# CON_AUDIO_AC99_NOMIC.net
KiCad netlist of a schematic drawn in Altium Designer
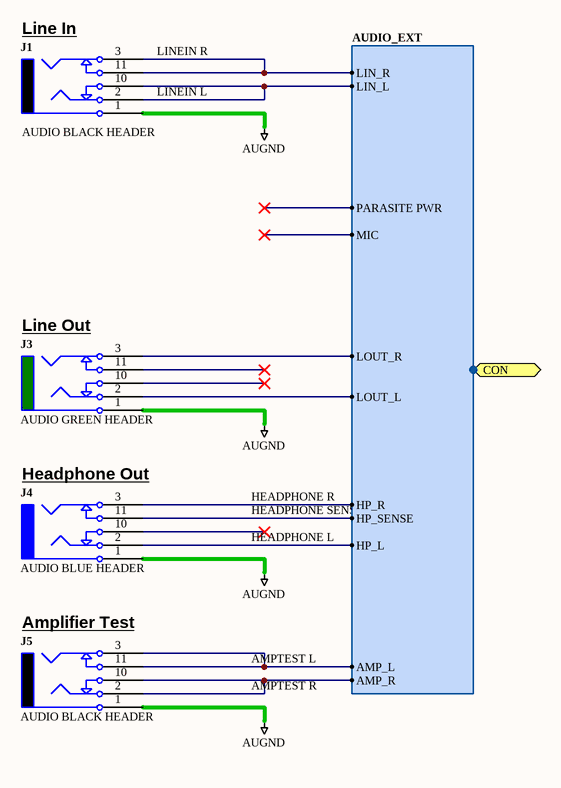
[diagram p0: CON_AUDIO_AC99_NOMIC.SchDoc]

(export (version "E")
  (design (tool "Eeschema 10.0.6"))
  (components
    (comp (ref "J1")
      (value "AUDIO BLACK HEADER")
      (footprint "TSH-3675")
      (libsource (lib "altium-import") (part "root_0_CON-PHONEJACK_"))
    )
    (comp (ref "J3")
      (value "AUDIO GREEN HEADER")
      (footprint "TSH-3675")
      (libsource (lib "altium-import") (part "root_0_CON-PHONEJACK_"))
    )
    (comp (ref "J4")
      (value "AUDIO BLUE HEADER")
      (footprint "TSH-3675")
      (libsource (lib "altium-import") (part "root_0_CON-PHONEJACK_"))
    )
    (comp (ref "J5")
      (value "AUDIO BLACK HEADER")
      (footprint "TSH-3675")
      (libsource (lib "altium-import") (part "root_0_CON-PHONEJACK_"))
    )
  )
  (nets
    (net (code "2") (name "/AMP_L") (class "Default")
      (node (ref "J5") (pin "11") (pintype "passive"))
      (node (ref "J5") (pin "3") (pintype "passive"))
    )
    (net (code "3") (name "/AMP_R") (class "Default")
      (node (ref "J5") (pin "10") (pintype "passive"))
      (node (ref "J5") (pin "2") (pintype "passive"))
    )
    (net (code "4") (name "/HP_L") (class "Default") (node (ref "J4") (pin "2") (pintype "passive")))
    (net (code "5") (name "/HP_R") (class "Default") (node (ref "J4") (pin "3") (pintype "passive")))
    (net (code "6") (name "/HP_SENSE") (class "Default") (node (ref "J4") (pin "11") (pintype "passive")))
    (net (code "7") (name "/LIN_L") (class "Default")
      (node (ref "J1") (pin "10") (pintype "passive"))
      (node (ref "J1") (pin "2") (pintype "passive"))
    )
    (net (code "8") (name "/LIN_R") (class "Default")
      (node (ref "J1") (pin "11") (pintype "passive"))
      (node (ref "J1") (pin "3") (pintype "passive"))
    )
    (net (code "9") (name "/LOUT_L") (class "Default") (node (ref "J3") (pin "2") (pintype "passive")))
    (net (code "10") (name "/LOUT_R") (class "Default") (node (ref "J3") (pin "3") (pintype "passive")))
    (net (code "14") (name "AUGND") (class "Default")
      (node (ref "J1") (pin "1") (pintype "passive"))
      (node (ref "J3") (pin "1") (pintype "passive"))
      (node (ref "J4") (pin "1") (pintype "passive"))
      (node (ref "J5") (pin "1") (pintype "passive"))
    )
    (net (code "15") (name "unconnected-(J3-Pad10)") (class "Default")
      (node (ref "J3") (pin "10") (pintype "passive+no_connect"))
    )
    (net (code "16") (name "unconnected-(J3-Pad11)") (class "Default")
      (node (ref "J3") (pin "11") (pintype "passive+no_connect"))
    )
    (net (code "17") (name "unconnected-(J4-Pad10)") (class "Default")
      (node (ref "J4") (pin "10") (pintype "passive+no_connect"))
    )
  )
)
